# Fuente.net
KiCad netlist of a schematic drawn in Altium Designer
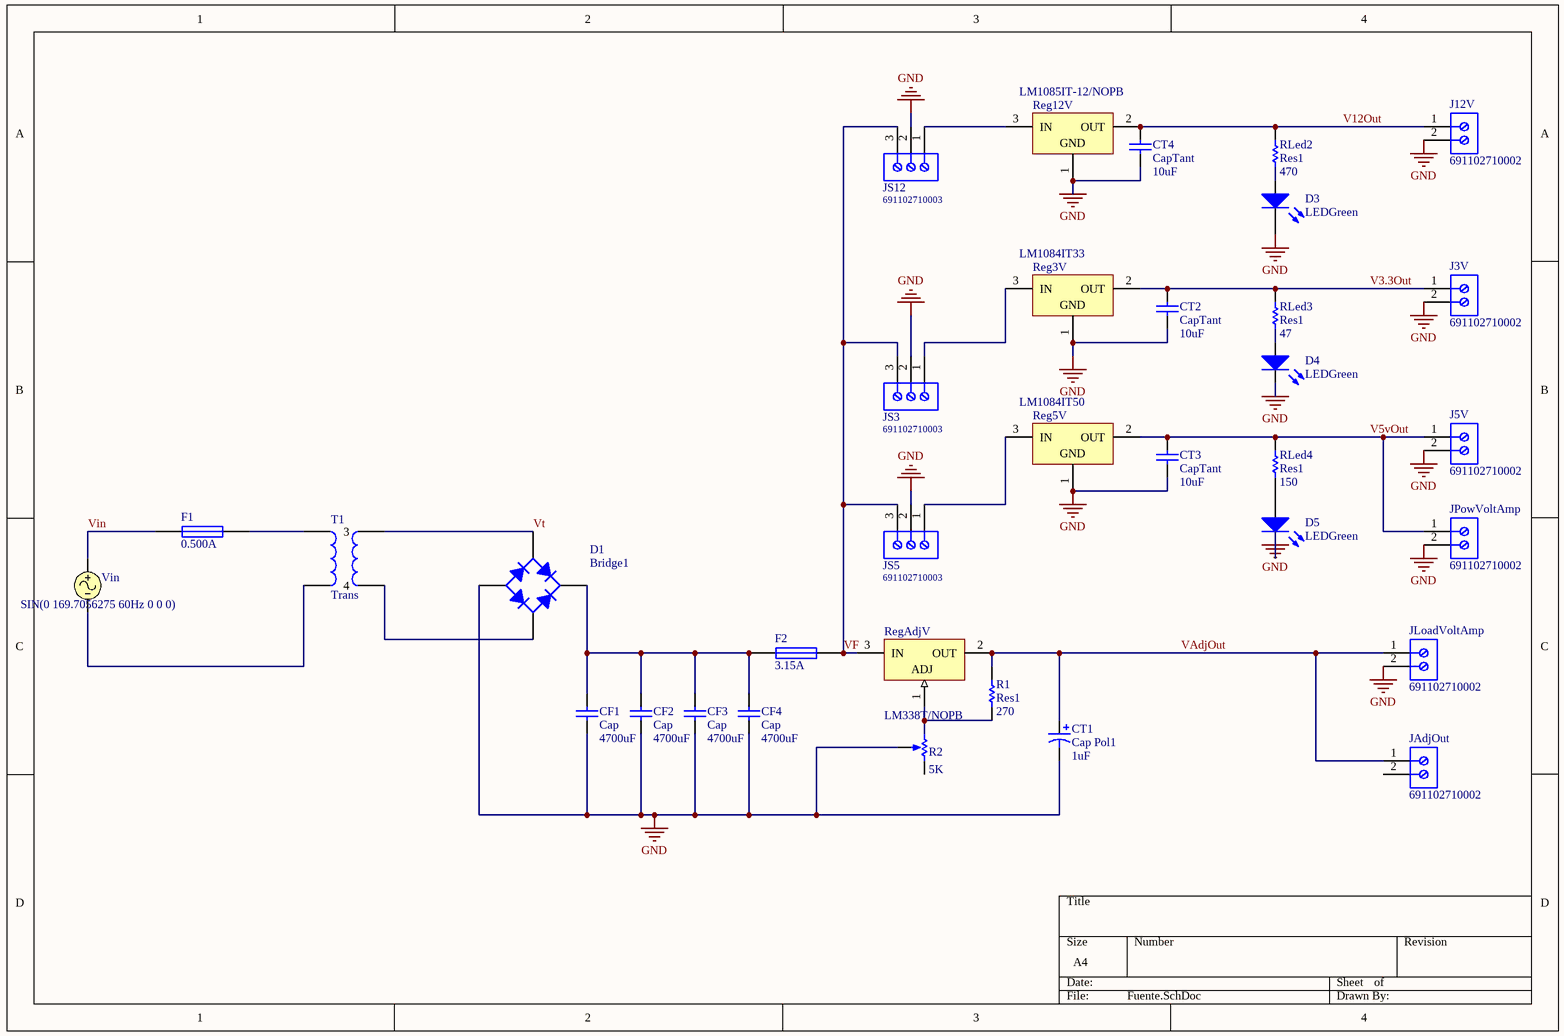
[diagram p0: Fuente.SchDoc]

(export (version "E")
  (design (tool "Eeschema 10.0.6"))
  (components
    (comp (ref "CF1")
      (value "Cap")
      (footprint "4700uF")
      (description "Capacitor")
      (fields (field (name "ALTIUM_VALUE") "4700uF") (field (name "PUBLISHER") "Altium Limited"))
      (libsource (lib "Miscellaneous Devices") (part "Cap"))
    )
    (comp (ref "CF2")
      (value "Cap")
      (footprint "4700uF")
      (description "Capacitor")
      (fields (field (name "ALTIUM_VALUE") "4700uF") (field (name "PUBLISHER") "Altium Limited"))
      (libsource (lib "Miscellaneous Devices") (part "Cap"))
    )
    (comp (ref "CF3")
      (value "Cap")
      (footprint "4700uF")
      (description "Capacitor")
      (fields (field (name "ALTIUM_VALUE") "4700uF") (field (name "PUBLISHER") "Altium Limited"))
      (libsource (lib "Miscellaneous Devices") (part "Cap"))
    )
    (comp (ref "CF4")
      (value "Cap")
      (footprint "4700uF")
      (description "Capacitor")
      (fields (field (name "ALTIUM_VALUE") "4700uF") (field (name "PUBLISHER") "Altium Limited"))
      (libsource (lib "Miscellaneous Devices") (part "Cap"))
    )
    (comp (ref "CT1")
      (value "Cap Pol1")
      (footprint "CAPPRD200W50D500H1250")
      (description "Polarized Capacitor (Radial)")
      (fields (field (name "ALTIUM_VALUE") "1uF") (field (name "PUBLISHER") "Altium Limited"))
      (libsource (lib "Miscellaneous Devices") (part "Cap Pol1"))
    )
    (comp (ref "CT2")
      (value "CapTant")
      (footprint "RAD-0.3")
      (description "Capacitor")
      (fields (field (name "ALTIUM_VALUE") "10uF") (field (name "PUBLISHER") "Altium Limited"))
      (libsource (lib "Miscellaneous Devices") (part "Cap"))
    )
    (comp (ref "CT3")
      (value "CapTant")
      (footprint "RAD-0.3")
      (description "Capacitor")
      (fields (field (name "ALTIUM_VALUE") "10uF") (field (name "PUBLISHER") "Altium Limited"))
      (libsource (lib "Miscellaneous Devices") (part "Cap"))
    )
    (comp (ref "CT4")
      (value "CapTant")
      (footprint "RAD-0.3")
      (description "Capacitor")
      (fields (field (name "ALTIUM_VALUE") "10uF") (field (name "PUBLISHER") "Altium Limited"))
      (libsource (lib "Miscellaneous Devices") (part "Cap"))
    )
    (comp (ref "D1")
      (value "Bridge1")
      (footprint "DIOB_GBJ2510")
      (description "Full Wave Diode Bridge")
      (fields (field (name "PUBLISHER") "Altium Limited"))
      (libsource (lib "Miscellaneous Devices") (part "Bridge1"))
    )
    (comp (ref "D3")
      (value "LEDGreen")
      (footprint "LEDRD254W57D500H1070")
      (description "Typical RED, GREEN, YELLOW, AMBER GaAs LED")
      (fields (field (name "PUBLISHER") "Altium Limited"))
      (libsource (lib "Miscellaneous Devices") (part "LED2"))
    )
    (comp (ref "D4")
      (value "LEDGreen")
      (footprint "LEDRD254W57D500H1070")
      (description "Typical RED, GREEN, YELLOW, AMBER GaAs LED")
      (fields (field (name "PUBLISHER") "Altium Limited"))
      (libsource (lib "Miscellaneous Devices") (part "LED2"))
    )
    (comp (ref "D5")
      (value "LEDGreen")
      (footprint "LEDRD254W57D500H1070")
      (description "Typical RED, GREEN, YELLOW, AMBER GaAs LED")
      (fields (field (name "PUBLISHER") "Altium Limited"))
      (libsource (lib "Miscellaneous Devices") (part "LED2"))
    )
    (comp (ref "F1")
      (value "0.500A")
      (footprint "PIN-W2/E2.8")
      (description "Fuse")
      (fields (field (name "PUBLISHER") "Altium Limited"))
      (libsource (lib "Miscellaneous Devices") (part "Fuse 1"))
    )
    (comp (ref "F2")
      (value "3.15A")
      (footprint "PIN-W2/E2.8")
      (fields (field (name "PUBLISHER") "Altium Limited"))
      (libsource (lib "Miscellaneous Devices") (part "Fuse 1"))
    )
    (comp (ref "J3V")
      (value "691102710002")
      (footprint "691102710002")
      (description "Series 102 - 5.00 mm Horizontal Entry Modular with Pressure Clamp WR-TBL, 2 pin")
      (fields (field (name "MANUFACTURER") "Wurth Elektronik") (field (name "PUBLISHER") "WurthElektronik"))
      (libsource (lib "Altium Content Vault") (part "WE-CN-1P-F-TB2"))
    )
    (comp (ref "J5V")
      (value "691102710002")
      (footprint "691102710002")
      (description "Series 102 - 5.00 mm Horizontal Entry Modular with Pressure Clamp WR-TBL, 2 pin")
      (fields (field (name "MANUFACTURER") "Wurth Elektronik") (field (name "PUBLISHER") "WurthElektronik"))
      (libsource (lib "Altium Content Vault") (part "WE-CN-1P-F-TB2"))
    )
    (comp (ref "J12V")
      (value "691102710002")
      (footprint "691102710002")
      (description "Series 102 - 5.00 mm Horizontal Entry Modular with Pressure Clamp WR-TBL, 2 pin")
      (fields (field (name "MANUFACTURER") "Wurth Elektronik") (field (name "PUBLISHER") "WurthElektronik"))
      (libsource (lib "Altium Content Vault") (part "WE-CN-1P-F-TB2"))
    )
    (comp (ref "JAdjOut")
      (value "691102710002")
      (footprint "691102710002")
      (description "Series 102 - 5.00 mm Horizontal Entry Modular with Pressure Clamp WR-TBL, 2 pin")
      (fields (field (name "MANUFACTURER") "Wurth Elektronik") (field (name "PUBLISHER") "WurthElektronik"))
      (libsource (lib "Altium Content Vault") (part "WE-CN-1P-F-TB2"))
    )
    (comp (ref "JLoadVoltAmp")
      (value "691102710002")
      (footprint "691102710002")
      (description "Series 102 - 5.00 mm Horizontal Entry Modular with Pressure Clamp WR-TBL, 2 pin")
      (fields (field (name "MANUFACTURER") "Wurth Elektronik") (field (name "PUBLISHER") "WurthElektronik"))
      (libsource (lib "Altium Content Vault") (part "WE-CN-1P-F-TB2"))
    )
    (comp (ref "JPowVoltAmp")
      (value "691102710002")
      (footprint "691102710002")
      (description "Series 102 - 5.00 mm Horizontal Entry Modular with Pressure Clamp WR-TBL, 2 pin")
      (fields (field (name "MANUFACTURER") "Wurth Elektronik") (field (name "PUBLISHER") "WurthElektronik"))
      (libsource (lib "Altium Content Vault") (part "WE-CN-1P-F-TB2"))
    )
    (comp (ref "JS3")
      (value "691102710003")
      (footprint "691102710003")
      (description "Series 102 - 5.00 mm Horizontal Entry Modular with Pressure Clamp WR-TBL, 3 pin")
      (fields (field (name "MANUFACTURER") "Wurth Elektronik") (field (name "PUBLISHER") "WurthElektronik"))
      (libsource (lib "Altium Content Vault") (part "WE-CN-1P-F-TB3"))
    )
    (comp (ref "JS5")
      (value "691102710003")
      (footprint "691102710003")
      (description "Series 102 - 5.00 mm Horizontal Entry Modular with Pressure Clamp WR-TBL, 3 pin")
      (fields (field (name "MANUFACTURER") "Wurth Elektronik") (field (name "PUBLISHER") "WurthElektronik"))
      (libsource (lib "Altium Content Vault") (part "WE-CN-1P-F-TB3"))
    )
    (comp (ref "JS12")
      (value "691102710003")
      (footprint "691102710003")
      (description "Series 102 - 5.00 mm Horizontal Entry Modular with Pressure Clamp WR-TBL, 3 pin")
      (fields (field (name "MANUFACTURER") "Wurth Elektronik") (field (name "PUBLISHER") "WurthElektronik"))
      (libsource (lib "Altium Content Vault") (part "WE-CN-1P-F-TB3"))
    )
    (comp (ref "R1")
      (value "Res1")
      (footprint "AXIAL-0.3")
      (description "Resistor")
      (fields (field (name "ALTIUM_VALUE") "270") (field (name "PUBLISHER") "Altium Limited"))
      (libsource (lib "Miscellaneous Devices") (part "Res1"))
    )
    (comp (ref "R2")
      (value "5K")
      (description "Potentiometer")
      (libsource (lib "Simulation Generic Components") (part "Potentiometer"))
    )
    (comp (ref "Reg3V")
      (value "LM1084IT33")
      (footprint "NDE0003A")
      (description "5A Low Dropout Positive Regulators, 3-pin TO-220, Pb-Free")
      (fields (field (name "MANUFACTURER") "Texas Instruments"))
      (libsource (lib "Altium Content Vault") (part "PM-REG-LM1086-SIL3"))
    )
    (comp (ref "Reg5V")
      (value "LM1084IT50")
      (footprint "NDE0003A")
      (description "5A Low Dropout Positive Regulators, 3-pin TO-220, Pb-Free")
      (fields (field (name "MANUFACTURER") "Texas Instruments"))
      (libsource (lib "Altium Content Vault") (part "PM-REG-LM1086-SIL3"))
    )
    (comp (ref "Reg12V")
      (value "LM1085IT-12/NOPB")
      (footprint "NDE0003A")
      (description "3A Low Dropout Positive Regulators, 3-pin TO-220, Pb-Free")
      (fields (field (name "MANUFACTURER") "Texas Instruments"))
      (libsource (lib "Altium Content Vault") (part "PM-REG-LM1086-SIL3"))
    )
    (comp (ref "RegAdjV")
      (value "LM338T/NOPB")
      (footprint "NDE0003A")
      (description "5 Amp Adjustable Regulator, 3-pin TO-220, Pb-Free")
      (fields (field (name "MANUFACTURER") "Texas Instruments"))
      (libsource (lib "Altium Content Vault") (part "PM-REG-LM1086ADJ-SIL3"))
    )
    (comp (ref "RLed2")
      (value "Res1")
      (footprint "AXIAL-0.3")
      (description "Resistor")
      (fields (field (name "ALTIUM_VALUE") "470") (field (name "PUBLISHER") "Altium Limited"))
      (libsource (lib "Miscellaneous Devices") (part "Res1"))
    )
    (comp (ref "RLed3")
      (value "Res1")
      (footprint "AXIAL-0.3")
      (description "Resistor")
      (fields (field (name "ALTIUM_VALUE") "47") (field (name "PUBLISHER") "Altium Limited"))
      (libsource (lib "Miscellaneous Devices") (part "Res1"))
    )
    (comp (ref "RLed4")
      (value "Res1")
      (footprint "AXIAL-0.3")
      (description "Resistor")
      (fields (field (name "ALTIUM_VALUE") "150") (field (name "PUBLISHER") "Altium Limited"))
      (libsource (lib "Miscellaneous Devices") (part "Res1"))
    )
    (comp (ref "T1")
      (value "Trans")
      (footprint "691102710002")
      (description "Transformer")
      (fields (field (name "PUBLISHER") "Altium Limited"))
      (libsource (lib "Miscellaneous Devices") (part "Trans"))
    )
    (comp (ref "Vin")
      (value "SIN(0 169.7056275 60Hz 0 0 0)")
      (description "Sinusoidal Voltage Source")
      (fields (field (name "PUBLISHER") "Altium Limited"))
      (libsource (lib "Simulation Sources") (part "VSIN"))
    )
  )
  (nets
    (net (code "1") (name "/V3.3Out") (class "Default")
      (node (ref "CT2") (pin "2") (pinfunction "2_2") (pintype "passive"))
      (node (ref "J3V") (pin "1") (pinfunction "1_1") (pintype "passive"))
      (node (ref "RLed3") (pin "2") (pinfunction "2_2") (pintype "passive"))
      (node (ref "Reg3V") (pin "2") (pinfunction "OUT_2") (pintype "power_in"))
    )
    (net (code "2") (name "/V5vOut") (class "Default")
      (node (ref "CT3") (pin "2") (pinfunction "2_2") (pintype "passive"))
      (node (ref "J5V") (pin "1") (pinfunction "1_1") (pintype "passive"))
      (node (ref "JPowVoltAmp") (pin "1") (pinfunction "1_1") (pintype "passive"))
      (node (ref "RLed4") (pin "2") (pinfunction "2_2") (pintype "passive"))
      (node (ref "Reg5V") (pin "2") (pinfunction "OUT_2") (pintype "power_in"))
    )
    (net (code "3") (name "/V12Out") (class "Default")
      (node (ref "CT4") (pin "2") (pinfunction "2_2") (pintype "passive"))
      (node (ref "J12V") (pin "1") (pinfunction "1_1") (pintype "passive"))
      (node (ref "RLed2") (pin "2") (pinfunction "2_2") (pintype "passive"))
      (node (ref "Reg12V") (pin "2") (pinfunction "OUT_2") (pintype "power_in"))
    )
    (net (code "4") (name "/VAdjOut") (class "Default")
      (node (ref "CT1") (pin "1") (pinfunction "1_1") (pintype "passive"))
      (node (ref "JAdjOut") (pin "1") (pinfunction "1_1") (pintype "passive"))
      (node (ref "JLoadVoltAmp") (pin "1") (pinfunction "1_1") (pintype "passive"))
      (node (ref "R1") (pin "2") (pinfunction "2_2") (pintype "passive"))
      (node (ref "RegAdjV") (pin "2") (pinfunction "OUT_2") (pintype "power_in"))
    )
    (net (code "5") (name "/VF") (class "Default")
      (node (ref "F2") (pin "2") (pinfunction "2_2") (pintype "passive"))
      (node (ref "JS12") (pin "3") (pinfunction "3_3") (pintype "passive"))
      (node (ref "JS3") (pin "3") (pinfunction "3_3") (pintype "passive"))
      (node (ref "JS5") (pin "3") (pinfunction "3_3") (pintype "passive"))
      (node (ref "RegAdjV") (pin "3") (pinfunction "IN_3") (pintype "power_in"))
    )
    (net (code "6") (name "/Vin") (class "Default")
      (node (ref "F1") (pin "1") (pinfunction "1_1") (pintype "passive"))
      (node (ref "Vin") (pin "1") (pinfunction "1_1") (pintype "passive"))
    )
    (net (code "7") (name "/Vt") (class "Default")
      (node (ref "D1") (pin "4") (pinfunction "C_4") (pintype "passive"))
      (node (ref "T1") (pin "3") (pinfunction "3_3") (pintype "passive"))
    )
    (net (code "8") (name "GND") (class "Default")
      (node (ref "CF1") (pin "1") (pinfunction "1_1") (pintype "passive"))
      (node (ref "CF2") (pin "1") (pinfunction "1_1") (pintype "passive"))
      (node (ref "CF3") (pin "1") (pinfunction "1_1") (pintype "passive"))
      (node (ref "CF4") (pin "1") (pinfunction "1_1") (pintype "passive"))
      (node (ref "CT1") (pin "2") (pinfunction "2_2") (pintype "passive"))
      (node (ref "CT2") (pin "1") (pinfunction "1_1") (pintype "passive"))
      (node (ref "CT3") (pin "1") (pinfunction "1_1") (pintype "passive"))
      (node (ref "CT4") (pin "1") (pinfunction "1_1") (pintype "passive"))
      (node (ref "D1") (pin "3") (pinfunction "A_3") (pintype "passive"))
      (node (ref "D3") (pin "2") (pinfunction "K_2") (pintype "passive"))
      (node (ref "D4") (pin "2") (pinfunction "K_2") (pintype "passive"))
      (node (ref "D5") (pin "2") (pinfunction "K_2") (pintype "passive"))
      (node (ref "J12V") (pin "2") (pinfunction "2_2") (pintype "passive"))
      (node (ref "J3V") (pin "2") (pinfunction "2_2") (pintype "passive"))
      (node (ref "J5V") (pin "2") (pinfunction "2_2") (pintype "passive"))
      (node (ref "JLoadVoltAmp") (pin "2") (pinfunction "2_2") (pintype "passive"))
      (node (ref "JPowVoltAmp") (pin "2") (pinfunction "2_2") (pintype "passive"))
      (node (ref "JS12") (pin "2") (pinfunction "2_2") (pintype "passive"))
      (node (ref "JS3") (pin "2") (pinfunction "2_2") (pintype "passive"))
      (node (ref "JS5") (pin "2") (pinfunction "2_2") (pintype "passive"))
      (node (ref "R2") (pin "3") (pinfunction "TAP_3") (pintype "passive"))
      (node (ref "Reg12V") (pin "1") (pinfunction "GND_1") (pintype "power_in"))
      (node (ref "Reg3V") (pin "1") (pinfunction "GND_1") (pintype "power_in"))
      (node (ref "Reg5V") (pin "1") (pinfunction "GND_1") (pintype "power_in"))
    )
    (net (code "9") (name "Net-(D1-C-Pad2)") (class "Default")
      (node (ref "D1") (pin "2") (pinfunction "C_2") (pintype "passive"))
      (node (ref "T1") (pin "4") (pinfunction "4_4") (pintype "passive"))
    )
    (net (code "10") (name "Net-(D1-K)") (class "Default")
      (node (ref "CF1") (pin "2") (pinfunction "2_2") (pintype "passive"))
      (node (ref "CF2") (pin "2") (pinfunction "2_2") (pintype "passive"))
      (node (ref "CF3") (pin "2") (pinfunction "2_2") (pintype "passive"))
      (node (ref "CF4") (pin "2") (pinfunction "2_2") (pintype "passive"))
      (node (ref "D1") (pin "1") (pinfunction "K_1") (pintype "passive"))
      (node (ref "F2") (pin "1") (pinfunction "1_1") (pintype "passive"))
    )
    (net (code "11") (name "Net-(D3-A)") (class "Default")
      (node (ref "D3") (pin "1") (pinfunction "A_1") (pintype "passive"))
      (node (ref "RLed2") (pin "1") (pinfunction "1_1") (pintype "passive"))
    )
    (net (code "12") (name "Net-(D4-A)") (class "Default")
      (node (ref "D4") (pin "1") (pinfunction "A_1") (pintype "passive"))
      (node (ref "RLed3") (pin "1") (pinfunction "1_1") (pintype "passive"))
    )
    (net (code "13") (name "Net-(D5-A)") (class "Default")
      (node (ref "D5") (pin "1") (pinfunction "A_1") (pintype "passive"))
      (node (ref "RLed4") (pin "1") (pinfunction "1_1") (pintype "passive"))
    )
    (net (code "14") (name "Net-(F1-Pad2)") (class "Default")
      (node (ref "F1") (pin "2") (pinfunction "2_2") (pintype "passive"))
      (node (ref "T1") (pin "1") (pinfunction "1_1") (pintype "passive"))
    )
    (net (code "15") (name "Net-(R2-TOP)") (class "Default")
      (node (ref "R1") (pin "1") (pinfunction "1_1") (pintype "passive"))
      (node (ref "R2") (pin "1") (pinfunction "TOP_1") (pintype "passive"))
      (node (ref "RegAdjV") (pin "1") (pinfunction "ADJ_1") (pintype "input"))
    )
    (net (code "16") (name "Net-(Reg3V-IN)") (class "Default")
      (node (ref "JS3") (pin "1") (pinfunction "1_1") (pintype "passive"))
      (node (ref "Reg3V") (pin "3") (pinfunction "IN_3") (pintype "power_in"))
    )
    (net (code "17") (name "Net-(Reg5V-IN)") (class "Default")
      (node (ref "JS5") (pin "1") (pinfunction "1_1") (pintype "passive"))
      (node (ref "Reg5V") (pin "3") (pinfunction "IN_3") (pintype "power_in"))
    )
    (net (code "18") (name "Net-(Reg12V-IN)") (class "Default")
      (node (ref "JS12") (pin "1") (pinfunction "1_1") (pintype "passive"))
      (node (ref "Reg12V") (pin "3") (pinfunction "IN_3") (pintype "power_in"))
    )
    (net (code "19") (name "Net-(T1-Pad2)") (class "Default")
      (node (ref "T1") (pin "2") (pinfunction "2_2") (pintype "passive"))
      (node (ref "Vin") (pin "2") (pinfunction "2_2") (pintype "passive"))
    )
    (net (code "20") (name "unconnected-(JAdjOut-Pad2)") (class "Default")
      (node (ref "JAdjOut") (pin "2") (pinfunction "2_2") (pintype "passive"))
    )
    (net (code "21") (name "unconnected-(R2-BOT-Pad2)") (class "Default")
      (node (ref "R2") (pin "2") (pinfunction "BOT_2") (pintype "passive"))
    )
  )
)
